# SCHEM_PDB_OFA.net
KiCad netlist of a schematic drawn in Altium Designer
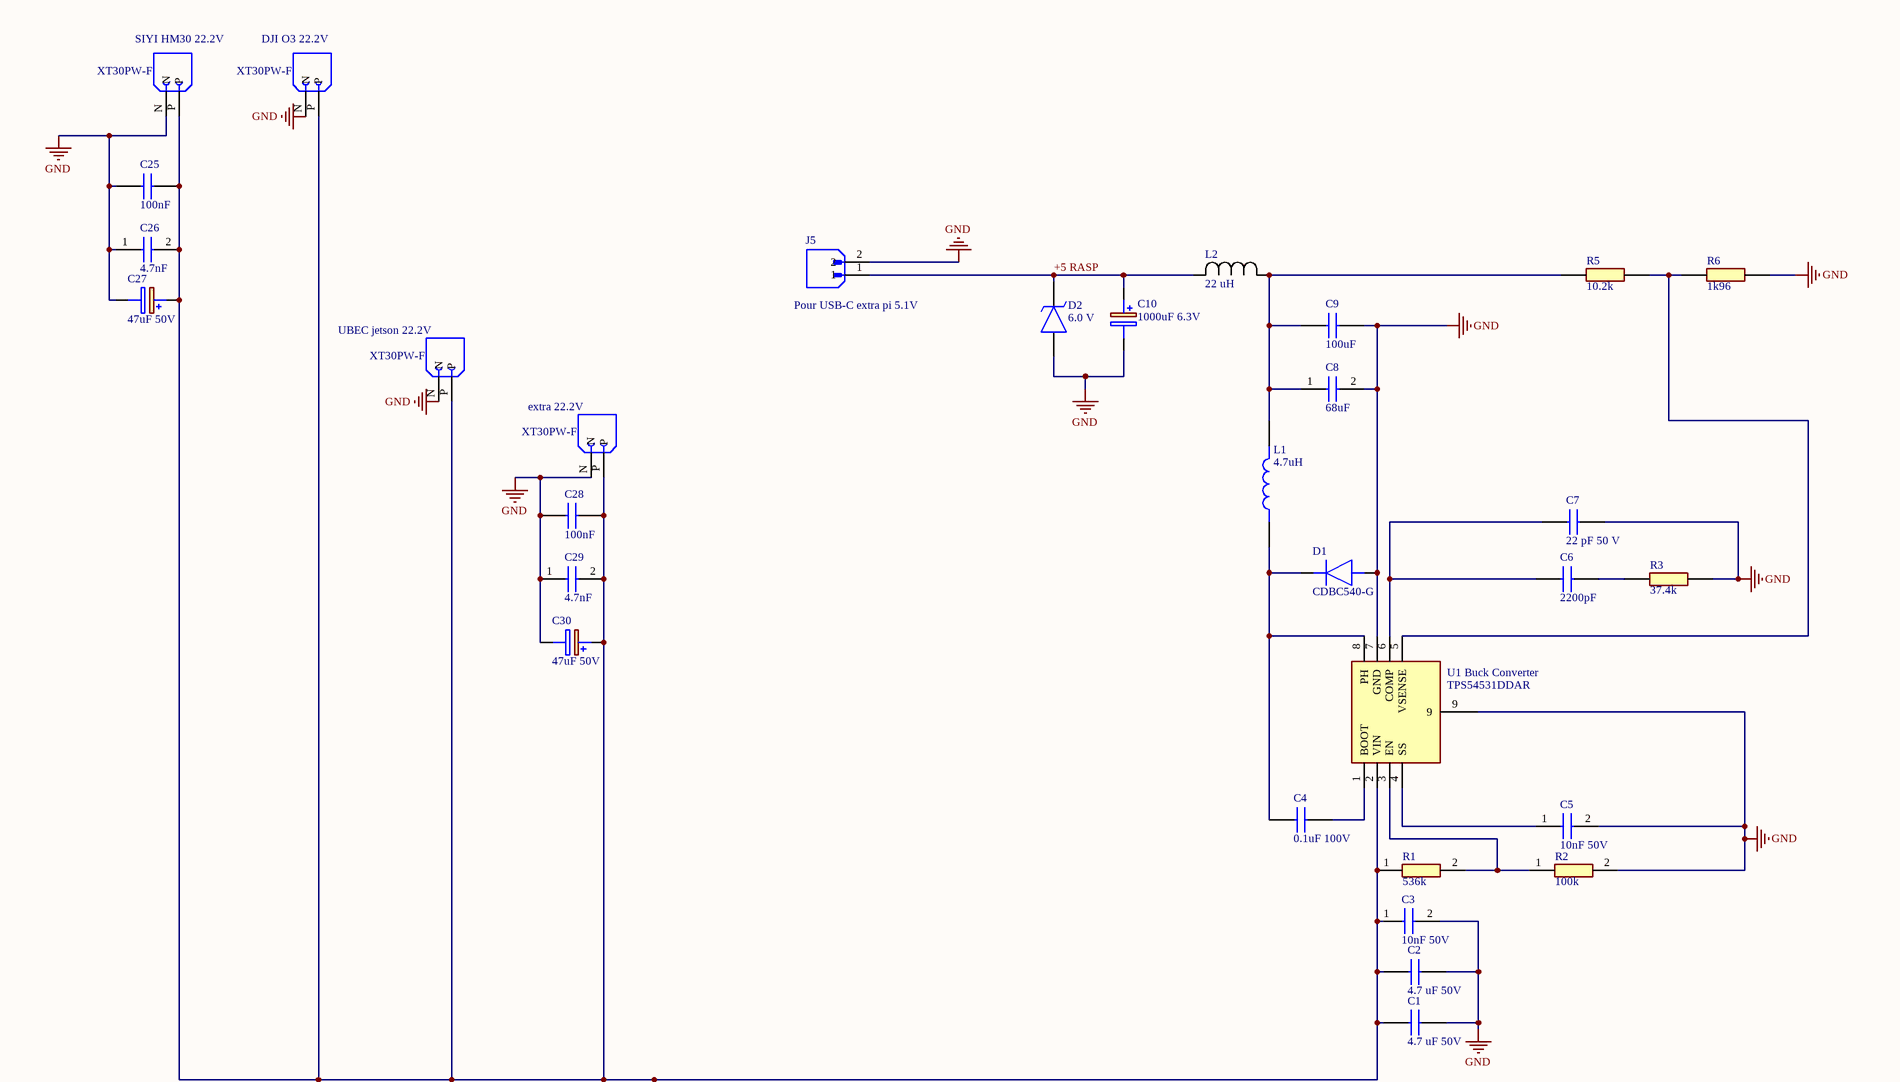
[diagram p0: SCHEM_PDB_OFA.SchDoc, top left]
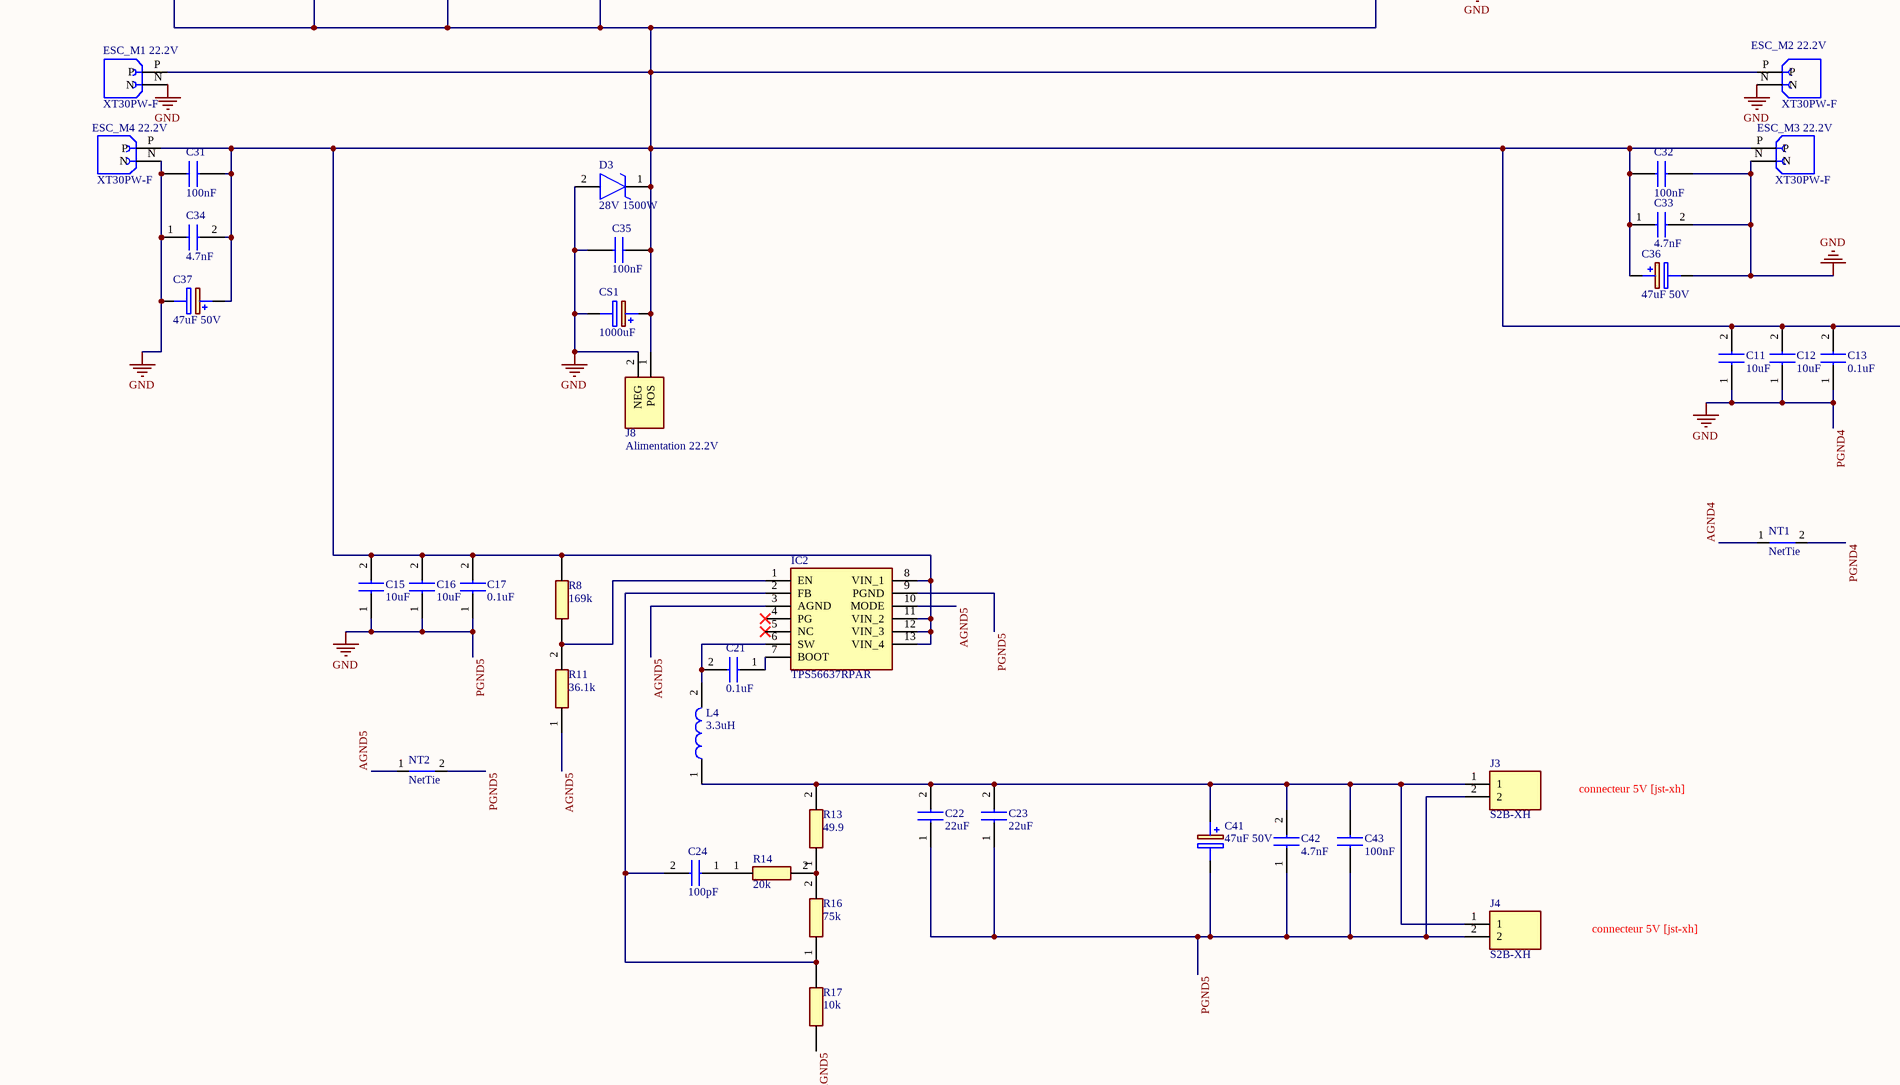
[diagram p1: SCHEM_PDB_OFA.SchDoc, bottom left]
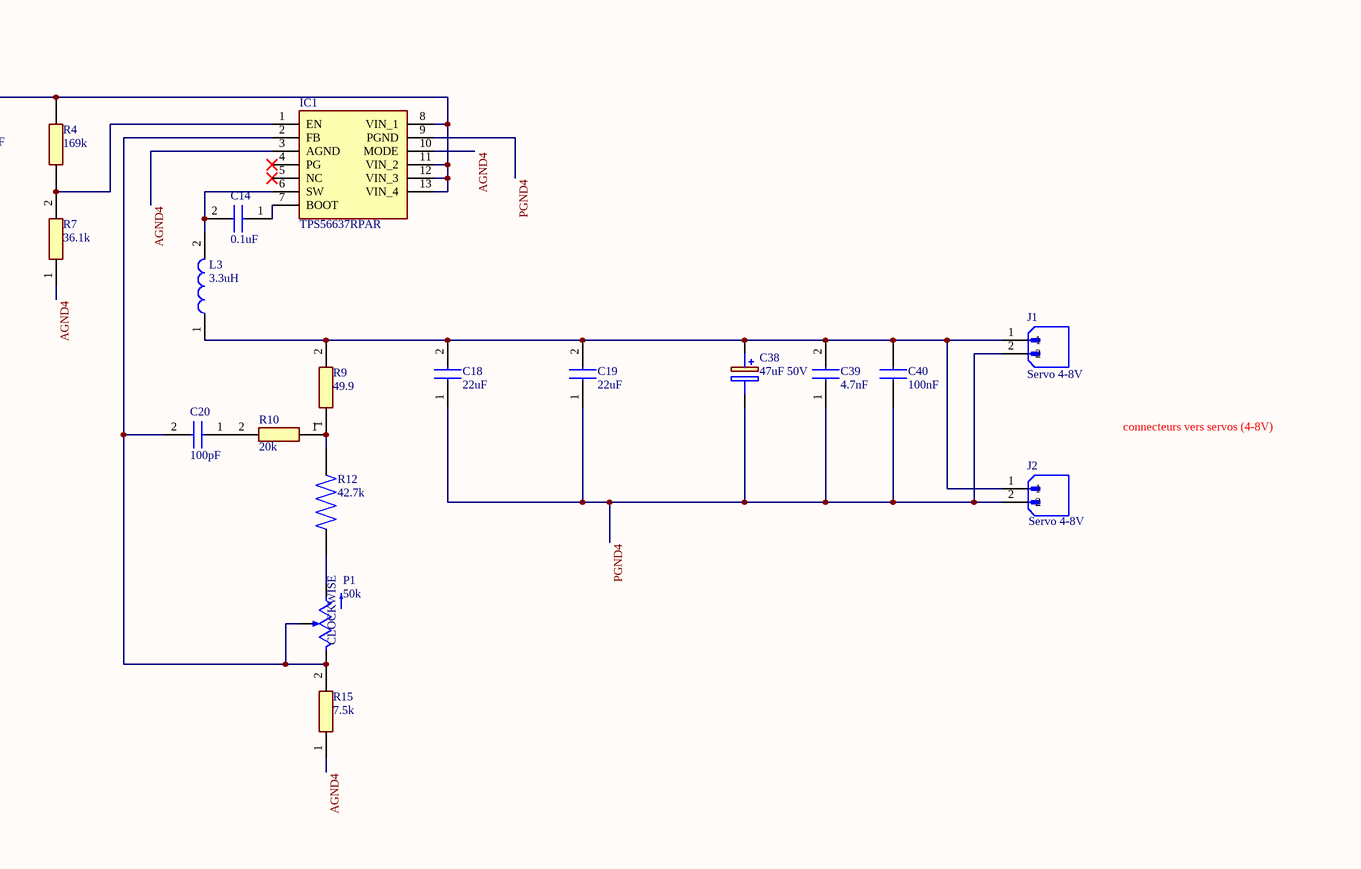
[diagram p2: SCHEM_PDB_OFA.SchDoc, bottom right]

(export (version "E")
  (design (tool "Eeschema 10.0.6"))
  (components
    (comp (ref "C1")
      (value "4.7 uF 50V")
      (footprint "CAPC2012X145N")
      (description "Capacitor")
      (fields
        (field (name "MANUFACTURER_PART_NUMBER") "GRM21BR61H475KE51L")
        (field (name "MOUSER PART NUMBER") "81-GRM21BR61H475KE1L")
      )
      (libsource (lib "Symbol_library") (part "GRM21BR61H475KE51L"))
    )
    (comp (ref "C2")
      (value "4.7 uF 50V")
      (footprint "CAPC2012X145N")
      (description "Capacitor")
      (fields
        (field (name "MANUFACTURER_PART_NUMBER") "GRM21BR61H475KE51L")
        (field (name "MOUSER PART NUMBER") "81-GRM21BR61H475KE1L")
      )
      (libsource (lib "Symbol_library") (part "GRM21BR61H475KE51L"))
    )
    (comp (ref "C3")
      (value "10nF 50V")
      (footprint "CAPC1608X90N")
      (description "Capacitor")
      (fields
        (field (name "MANUFACTURER_PART_NUMBER") "CL10B103KB8NNNC")
        (field (name "MOUSER PART NUMBER") "187-CL10B103KB8NNNC")
      )
      (libsource (lib "Symbol_library") (part "CL10B103KB8NNNC"))
    )
    (comp (ref "C4")
      (value "0.1uF 100V")
      (footprint "CAPC2012X145N")
      (description "Capacitor")
      (fields
        (field (name "MANUFACTURER_PART_NUMBER") "C2012X7R2A104K125AA")
        (field (name "MOUSER PART NUMBER") "810-C2012X7R2A104K")
      )
      (libsource (lib "Symbol_library") (part "C2012X7R2A104K125AA"))
    )
    (comp (ref "C5")
      (value "10nF 50V")
      (footprint "CAPC1608X90N")
      (description "Capacitor")
      (fields
        (field (name "MANUFACTURER_PART_NUMBER") "CL10B103KB8NNNC")
        (field (name "MOUSER PART NUMBER") "187-CL10B103KB8NNNC")
      )
      (libsource (lib "Symbol_library") (part "CL10B103KB8NNNC"))
    )
    (comp (ref "C6")
      (value "2200pF")
      (footprint "CAPC3216X130N")
      (description "Capacitor 2200pF 630V")
      (fields (field (name "MANUFACTURER_PART_NUMBER") "CGA5H4C0G2J222J115AA"))
      (libsource (lib "Symbol_library") (part "CGA5H4C0G2J222J115AA"))
    )
    (comp (ref "C7")
      (value "22 pF 50 V")
      (footprint "CAPC2012X70N")
      (description "Capacitor")
      (fields
        (field (name "MANUFACTURER_PART_NUMBER") "CC0805JRNPO9BN220")
        (field (name "MOUSER PART NUMBER") "603-CC805JRNPO9BN220")
      )
      (libsource (lib "Symbol_library") (part "CC0805JRNPO9BN220"))
    )
    (comp (ref "C8")
      (value "68uF")
      (footprint "CAPC3216X180N")
      (description "Capacitor de 68uF")
      (fields
        (field (name "MANUFACTURER_PART_NUMBER") "C3216X5R0J686M160AB")
        (field (name "MOUSER PART NUMBER") "810-C3216X5R0J686M1B")
      )
      (libsource (lib "Symbol_library") (part "C3216X5R0J686M160AB"))
    )
    (comp (ref "C9")
      (value "100uF")
      (footprint "GRM31x")
      (description "Capacitor")
      (fields
        (field (name "MANUFACTURER_PART_NUMBER") "GRM31CR60J107KEA8L")
        (field (name "MOUSER PART NUMBER") "81-GRM31CR60J107KE8L")
      )
      (libsource (lib "Symbol_library") (part "GRM31CR60J107KEA8L"))
    )
    (comp (ref "C10")
      (value "1000uF 6.3V")
      (footprint "CAPAE830X1050N")
      (description "Capacitor Polarised")
      (fields
        (field (name "MANUFACTURER_PART_NUMBER") "UCD0J102MNL1GS")
        (field (name "MOUSER PART NUMBER") "647-UCD0J102MNL1GS")
      )
      (libsource (lib "Symbol_library") (part "UCD0J102MNL1GS"))
    )
    (comp (ref "C11")
      (value "10uF")
      (footprint "CAPC3225X280N")
      (description "Capacitor")
      (fields (field (name "MANUFACTURER_PART_NUMBER") "AGC1210X7R500-106KNE"))
      (libsource (lib "Symbol_library") (part "AGC1210X7R500-106KNE"))
    )
    (comp (ref "C12")
      (value "10uF")
      (footprint "CAPC3225X280N")
      (description "Capacitor")
      (fields (field (name "MANUFACTURER_PART_NUMBER") "AGC1210X7R500-106KNE"))
      (libsource (lib "Symbol_library") (part "AGC1210X7R500-106KNE"))
    )
    (comp (ref "C13")
      (value "0.1uF")
      (footprint "C0603")
      (description "Capacitor")
      (fields
        (field (name "MANUFACTURER_PART_NUMBER") "C0603C104K5RACTU")
        (field (name "MOUSER PART NUMBER") "80-C0603C104K5R")
      )
      (libsource (lib "Symbol_library") (part "C0603C104K5RACTU"))
    )
    (comp (ref "C14")
      (value "0.1uF")
      (footprint "C0603")
      (description "Capacitor")
      (fields
        (field (name "MANUFACTURER_PART_NUMBER") "C0603C104K5RACTU")
        (field (name "MOUSER PART NUMBER") "80-C0603C104K5R")
      )
      (libsource (lib "Symbol_library") (part "C0603C104K5RACTU"))
    )
    (comp (ref "C15")
      (value "10uF")
      (footprint "CAPC3225X280N")
      (description "Capacitor")
      (fields (field (name "MANUFACTURER_PART_NUMBER") "AGC1210X7R500-106KNE"))
      (libsource (lib "Symbol_library") (part "AGC1210X7R500-106KNE"))
    )
    (comp (ref "C16")
      (value "10uF")
      (footprint "CAPC3225X280N")
      (description "Capacitor")
      (fields (field (name "MANUFACTURER_PART_NUMBER") "AGC1210X7R500-106KNE"))
      (libsource (lib "Symbol_library") (part "AGC1210X7R500-106KNE"))
    )
    (comp (ref "C17")
      (value "0.1uF")
      (footprint "C0603")
      (description "Capacitor")
      (fields
        (field (name "MANUFACTURER_PART_NUMBER") "C0603C104K5RACTU")
        (field (name "MOUSER PART NUMBER") "80-C0603C104K5R")
      )
      (libsource (lib "Symbol_library") (part "C0603C104K5RACTU"))
    )
    (comp (ref "C18")
      (value "22uF")
      (footprint "CAPC2012X145N")
      (description "Capacitor, 35V")
      (fields
        (field (name "MANUFACTURER_PART_NUMBER") "C2012X5R1V226M125AC")
        (field (name "MOUSER PART NUMBER") "810-C2012X5R1V226MAC")
      )
      (libsource (lib "Symbol_library") (part "C2012X5R1V226M125AC"))
    )
    (comp (ref "C19")
      (value "22uF")
      (footprint "CAPC2012X145N")
      (description "Capacitor, 35V")
      (fields
        (field (name "MANUFACTURER_PART_NUMBER") "C2012X5R1V226M125AC")
        (field (name "MOUSER PART NUMBER") "810-C2012X5R1V226MAC")
      )
      (libsource (lib "Symbol_library") (part "C2012X5R1V226M125AC"))
    )
    (comp (ref "C20")
      (value "100pF")
      (footprint "GRM1885C1H101JA01D")
      (description "Capacitor")
      (fields
        (field (name "MANUFACTURER_PART_NUMBER") "GRM1885C1H101JA01D")
        (field (name "MOUSER PART NUMBER") "81-GRM39C101J50")
      )
      (libsource (lib "Symbol_library") (part "GRM1885C1H101JA01D"))
    )
    (comp (ref "C21")
      (value "0.1uF")
      (footprint "C0603")
      (description "Capacitor")
      (fields
        (field (name "MANUFACTURER_PART_NUMBER") "C0603C104K5RACTU")
        (field (name "MOUSER PART NUMBER") "80-C0603C104K5R")
      )
      (libsource (lib "Symbol_library") (part "C0603C104K5RACTU"))
    )
    (comp (ref "C22")
      (value "22uF")
      (footprint "CAPC2012X145N")
      (description "Capacitor, 35V")
      (fields
        (field (name "MANUFACTURER_PART_NUMBER") "C2012X5R1V226M125AC")
        (field (name "MOUSER PART NUMBER") "810-C2012X5R1V226MAC")
      )
      (libsource (lib "Symbol_library") (part "C2012X5R1V226M125AC"))
    )
    (comp (ref "C23")
      (value "22uF")
      (footprint "CAPC2012X145N")
      (description "Capacitor, 35V")
      (fields
        (field (name "MANUFACTURER_PART_NUMBER") "C2012X5R1V226M125AC")
        (field (name "MOUSER PART NUMBER") "810-C2012X5R1V226MAC")
      )
      (libsource (lib "Symbol_library") (part "C2012X5R1V226M125AC"))
    )
    (comp (ref "C24")
      (value "100pF")
      (footprint "GRM1885C1H101JA01D")
      (description "Capacitor")
      (fields
        (field (name "MANUFACTURER_PART_NUMBER") "GRM1885C1H101JA01D")
        (field (name "MOUSER PART NUMBER") "81-GRM39C101J50")
      )
      (libsource (lib "Symbol_library") (part "GRM1885C1H101JA01D"))
    )
    (comp (ref "C25")
      (value "100nF")
      (footprint "C1206")
      (description "Capacitor, 100V max")
      (fields
        (field (name "MANUFACTURER_PART_NUMBER") "C1206C104K1RACTU")
        (field (name "MOUSER PART NUMBER") "80-C1206C104K1R")
      )
      (libsource (lib "Symbol_library") (part "C1206C104K1RACTU"))
    )
    (comp (ref "C26")
      (value "4.7nF")
      (footprint "C1206")
      (description "Capacitor, 50V max")
      (fields
        (field (name "MANUFACTURER_PART_NUMBER") "C1206C472K5RACTU")
        (field (name "MOUSER PART NUMBER") "80-C1206C472K5R")
      )
      (libsource (lib "Symbol_library") (part "C1206C472K5RACTU"))
    )
    (comp (ref "C27")
      (value "47uF 50V")
      (footprint "CAPPRD250W50D655H1250")
      (description "Capacitor Polarised, 47uF, 50V")
      (fields
        (field (name "MANUFACTURER_PART_NUMBER") "50YXJ47M6.3X11")
        (field (name "MOUSER PART NUMBER") "232-50YXJ47M6.3X11")
      )
      (libsource (lib "") (part "50YXJ47M6.3X11_1"))
    )
    (comp (ref "C28")
      (value "100nF")
      (footprint "C1206")
      (description "Capacitor, 100V max")
      (fields
        (field (name "MANUFACTURER_PART_NUMBER") "C1206C104K1RACTU")
        (field (name "MOUSER PART NUMBER") "80-C1206C104K1R")
      )
      (libsource (lib "Symbol_library") (part "C1206C104K1RACTU"))
    )
    (comp (ref "C29")
      (value "4.7nF")
      (footprint "C1206")
      (description "Capacitor, 50V max")
      (fields
        (field (name "MANUFACTURER_PART_NUMBER") "C1206C472K5RACTU")
        (field (name "MOUSER PART NUMBER") "80-C1206C472K5R")
      )
      (libsource (lib "Symbol_library") (part "C1206C472K5RACTU"))
    )
    (comp (ref "C30")
      (value "47uF 50V")
      (footprint "CAPPRD250W50D655H1250")
      (description "Capacitor Polarised, 47uF, 50V")
      (fields
        (field (name "MANUFACTURER_PART_NUMBER") "50YXJ47M6.3X11")
        (field (name "MOUSER PART NUMBER") "232-50YXJ47M6.3X11")
      )
      (libsource (lib "") (part "50YXJ47M6.3X11_1"))
    )
    (comp (ref "C31")
      (value "100nF")
      (footprint "C1206")
      (description "Capacitor, 100V max")
      (fields
        (field (name "MANUFACTURER_PART_NUMBER") "C1206C104K1RACTU")
        (field (name "MOUSER PART NUMBER") "80-C1206C104K1R")
      )
      (libsource (lib "Symbol_library") (part "C1206C104K1RACTU"))
    )
    (comp (ref "C32")
      (value "100nF")
      (footprint "C1206")
      (description "Capacitor, 100V max")
      (fields
        (field (name "MANUFACTURER_PART_NUMBER") "C1206C104K1RACTU")
        (field (name "MOUSER PART NUMBER") "80-C1206C104K1R")
      )
      (libsource (lib "Symbol_library") (part "C1206C104K1RACTU"))
    )
    (comp (ref "C33")
      (value "4.7nF")
      (footprint "C1206")
      (description "Capacitor, 50V max")
      (fields
        (field (name "MANUFACTURER_PART_NUMBER") "C1206C472K5RACTU")
        (field (name "MOUSER PART NUMBER") "80-C1206C472K5R")
      )
      (libsource (lib "Symbol_library") (part "C1206C472K5RACTU"))
    )
    (comp (ref "C34")
      (value "4.7nF")
      (footprint "C1206")
      (description "Capacitor, 50V max")
      (fields
        (field (name "MANUFACTURER_PART_NUMBER") "C1206C472K5RACTU")
        (field (name "MOUSER PART NUMBER") "80-C1206C472K5R")
      )
      (libsource (lib "Symbol_library") (part "C1206C472K5RACTU"))
    )
    (comp (ref "C35")
      (value "100nF")
      (footprint "C1206")
      (description "Capacitor, 100V max")
      (fields
        (field (name "MANUFACTURER_PART_NUMBER") "C1206C104K1RACTU")
        (field (name "MOUSER PART NUMBER") "80-C1206C104K1R")
      )
      (libsource (lib "Symbol_library") (part "C1206C104K1RACTU"))
    )
    (comp (ref "C36")
      (value "47uF 50V")
      (footprint "CAPPRD250W50D655H1250")
      (description "Capacitor Polarised, 47uF, 50V")
      (fields
        (field (name "MANUFACTURER_PART_NUMBER") "50YXJ47M6.3X11")
        (field (name "MOUSER PART NUMBER") "232-50YXJ47M6.3X11")
      )
      (libsource (lib "Symbol_library") (part "50YXJ47M6.3X11"))
    )
    (comp (ref "C37")
      (value "47uF 50V")
      (footprint "CAPPRD250W50D655H1250")
      (description "Capacitor Polarised, 47uF, 50V")
      (fields
        (field (name "MANUFACTURER_PART_NUMBER") "50YXJ47M6.3X11")
        (field (name "MOUSER PART NUMBER") "232-50YXJ47M6.3X11")
      )
      (libsource (lib "") (part "50YXJ47M6.3X11_1"))
    )
    (comp (ref "C38")
      (value "47uF 50V")
      (footprint "CAPPRD250W50D655H1250")
      (description "Capacitor Polarised, 47uF, 50V")
      (fields
        (field (name "MANUFACTURER_PART_NUMBER") "50YXJ47M6.3X11")
        (field (name "MOUSER PART NUMBER") "232-50YXJ47M6.3X11")
      )
      (libsource (lib "") (part "50YXJ47M6.3X11_2"))
    )
    (comp (ref "C39")
      (value "4.7nF")
      (footprint "C1206")
      (description "Capacitor, 50V max")
      (fields
        (field (name "MANUFACTURER_PART_NUMBER") "C1206C472K5RACTU")
        (field (name "MOUSER PART NUMBER") "80-C1206C472K5R")
      )
      (libsource (lib "Symbol_library") (part "C1206C472K5RACTU"))
    )
    (comp (ref "C40")
      (value "100nF")
      (footprint "C1206")
      (description "Capacitor, 100V max")
      (fields
        (field (name "MANUFACTURER_PART_NUMBER") "C1206C104K1RACTU")
        (field (name "MOUSER PART NUMBER") "80-C1206C104K1R")
      )
      (libsource (lib "Symbol_library") (part "C1206C104K1RACTU"))
    )
    (comp (ref "C41")
      (value "47uF 50V")
      (footprint "CAPPRD250W50D655H1250")
      (description "Capacitor Polarised, 47uF, 50V")
      (fields
        (field (name "MANUFACTURER_PART_NUMBER") "50YXJ47M6.3X11")
        (field (name "MOUSER PART NUMBER") "232-50YXJ47M6.3X11")
      )
      (libsource (lib "") (part "50YXJ47M6.3X11_2"))
    )
    (comp (ref "C42")
      (value "4.7nF")
      (footprint "C1206")
      (description "Capacitor, 50V max")
      (fields
        (field (name "MANUFACTURER_PART_NUMBER") "C1206C472K5RACTU")
        (field (name "MOUSER PART NUMBER") "80-C1206C472K5R")
      )
      (libsource (lib "Symbol_library") (part "C1206C472K5RACTU"))
    )
    (comp (ref "C43")
      (value "100nF")
      (footprint "C1206")
      (description "Capacitor, 100V max")
      (fields
        (field (name "MANUFACTURER_PART_NUMBER") "C1206C104K1RACTU")
        (field (name "MOUSER PART NUMBER") "80-C1206C104K1R")
      )
      (libsource (lib "Symbol_library") (part "C1206C104K1RACTU"))
    )
    (comp (ref "CS1")
      (value "1000uF")
      (footprint "CAPPRD500W60D1025H2150")
      (description "Capacitor Polarised")
      (fields
        (field (name "MANUFACTURER_PART_NUMBER") "35PX1000MEFC10X20")
        (field (name "MOUSER PART NUMBER") "232-35PX1000MEFC10X2")
      )
      (libsource (lib "Symbol_library") (part "35PX1000MEFC10X20"))
    )
    (comp (ref "D1")
      (value "CDBC540-G")
      (footprint "DIOM8059X290N")
      (description "Diode")
      (fields (field (name "MOUSER PART NUMBER") "750-CDBC540-G"))
      (libsource (lib "Symbol_library") (part "CDBC540-G"))
    )
    (comp (ref "D2")
      (value "6.0 V")
      (footprint "SMBJ12A")
      (description "TVS Diode (Uni-directional)")
      (fields (field (name "MANUFACTURER_PART_NUMBER") "SMBJ6.0A"))
      (libsource (lib "Symbol_library") (part "SMBJ6.0A"))
    )
    (comp (ref "D3")
      (value "28V 1500W")
      (footprint "DIOM7959X262N")
      (description "TVS Diode, 1500W, 28V")
      (fields
        (field (name "MANUFACTURER_PART_NUMBER") "SMCJ28A")
        (field (name "MOUSER PART NUMBER") "652-SMCJ28A")
      )
      (libsource (lib "Symbol_library") (part "SMCJ28A"))
    )
    (comp (ref "DJI O3 22.2V")
      (value "XT30PW-F")
      (footprint "AMASS_XT30PW-F")
      (description "Socket; DC supply; XT30; female; PIN: 2; on PCBs; THT; yellow; 15A")
      (fields (field (name "MF") "amass"))
      (libsource (lib "Symbol_library") (part "XT30PW-F"))
    )
    (comp (ref "ESC_M1 22.2V")
      (value "XT30PW-F")
      (footprint "AMASS_XT30PW-F")
      (description "Socket; DC supply; XT30; female; PIN: 2; on PCBs; THT; yellow; 15A")
      (fields (field (name "MF") "amass"))
      (libsource (lib "Symbol_library") (part "XT30PW-F"))
    )
    (comp (ref "ESC_M2 22.2V")
      (value "XT30PW-F")
      (footprint "AMASS_XT30PW-F")
      (description "Socket; DC supply; XT30; female; PIN: 2; on PCBs; THT; yellow; 15A")
      (fields (field (name "MF") "amass"))
      (libsource (lib "") (part "XT30PW-F_1"))
    )
    (comp (ref "ESC_M3 22.2V")
      (value "XT30PW-F")
      (footprint "AMASS_XT30PW-F")
      (description "Socket; DC supply; XT30; female; PIN: 2; on PCBs; THT; yellow; 15A")
      (fields (field (name "MF") "amass"))
      (libsource (lib "") (part "XT30PW-F_1"))
    )
    (comp (ref "ESC_M4 22.2V")
      (value "XT30PW-F")
      (footprint "AMASS_XT30PW-F")
      (description "Socket; DC supply; XT30; female; PIN: 2; on PCBs; THT; yellow; 15A")
      (fields (field (name "MF") "amass"))
      (libsource (lib "Symbol_library") (part "XT30PW-F"))
    )
    (comp (ref "extra 22.2V")
      (value "XT30PW-F")
      (footprint "AMASS_XT30PW-F")
      (description "Socket; DC supply; XT30; female; PIN: 2; on PCBs; THT; yellow; 15A")
      (fields (field (name "MF") "amass"))
      (libsource (lib "Symbol_library") (part "XT30PW-F"))
    )
    (comp (ref "IC1")
      (value "TPS56637RPAR")
      (footprint "TPS56637RPAR")
      (description "Integrated Circuit")
      (fields (field (name "MOUSER PART NUMBER") "595-TPS56637RPAR"))
      (libsource (lib "Symbol_library") (part "TPS56637RPAR"))
    )
    (comp (ref "IC2")
      (value "TPS56637RPAR")
      (footprint "TPS56637RPAR")
      (description "Integrated Circuit")
      (fields (field (name "MOUSER PART NUMBER") "595-TPS56637RPAR"))
      (libsource (lib "Symbol_library") (part "TPS56637RPAR"))
    )
    (comp (ref "J1")
      (value "Servo 4-8V")
      (footprint "JST_B2PS-VH_(LF)(SN)")
      (description "Connector Header Through Hole, Right Angle 2 position 0.156 (3.96mm)")
      (fields (field (name "MF") "JST") (field (name "MP") "B2PS-VH (LF)(SN)"))
      (libsource (lib "") (part "B2PS-VH_(LF)(SN)_1"))
    )
    (comp (ref "J2")
      (value "Servo 4-8V")
      (footprint "JST_B2PS-VH_(LF)(SN)")
      (description "Connector Header Through Hole, Right Angle 2 position 0.156 (3.96mm)")
      (fields (field (name "MF") "JST") (field (name "MP") "B2PS-VH (LF)(SN)"))
      (libsource (lib "") (part "B2PS-VH_(LF)(SN)_1"))
    )
    (comp (ref "J3")
      (value "S2B-XH")
      (footprint "S2BXHA1LFSN")
      (description "CONN HEADER R/A 2POS 2.5MM")
      (fields (field (name "MANUFACTURER_PART_NUMBER") "S2B-XH-A-1(LF)(SN)"))
      (libsource (lib "Symbol_library") (part "S2B-XH-A-1_LF__SN_"))
    )
    (comp (ref "J4")
      (value "S2B-XH")
      (footprint "S2BXHA1LFSN")
      (description "CONN HEADER R/A 2POS 2.5MM")
      (fields (field (name "MANUFACTURER_PART_NUMBER") "S2B-XH-A-1(LF)(SN)"))
      (libsource (lib "Symbol_library") (part "S2B-XH-A-1_LF__SN_"))
    )
    (comp (ref "J5")
      (value "Pour USB-C extra pi 5.1V")
      (footprint "JST_B2PS-VH_(LF)(SN)")
      (description "Connector Header Through Hole, Right Angle 2 position 0.156 (3.96mm)")
      (fields (field (name "MF") "JST") (field (name "MP") "B2PS-VH (LF)(SN)"))
      (libsource (lib "Symbol_library") (part "B2PS-VH_(LF)(SN)"))
    )
    (comp (ref "J8")
      (value "Alimentation 22.2V")
      (footprint "AMASS_XT60PW-M")
      (description "Socket, DC supply, male, PIN: 2")
      (fields (field (name "MF") "AMASS") (field (name "MP") "XT60PW-M"))
      (libsource (lib "Symbol_library") (part "XT60PW-M"))
    )
    (comp (ref "L1")
      (value "4.7uH")
      (footprint "IND_ECS-MPIL0530-4R7MC")
      (description "4.7 µH Shielded Molded Inductor 5 A 60mOhm Max Nonstandard -")
      (fields (field (name "MF") "ECS Inc.") (field (name "MP") "ECS-MPIL0530-4R7MC"))
      (libsource (lib "Symbol_library") (part "ECS-MPIL0530-4R7MC"))
    )
    (comp (ref "L2")
      (value "22 uH")
      (footprint "IND_104CDMCCDS_SUM")
      (description "Bobine de 22 uH, 5 A")
      (fields
        (field (name "MANUFACTURER_PART_NUMBER") "104CDMCCDS-220MC")
        (field (name "COPYRIGHT") "Copyright (C) 2025 Ultra Librarian. All rights reserved.")
      )
      (libsource (lib "Symbol_library") (part "104CDMCCDS-220MC"))
    )
    (comp (ref "L3")
      (value "3.3uH")
      (footprint "INDM3225X240N")
      (description "Inductor")
      (fields (field (name "MANUFACTURER_PART_NUMBER") "NLV32T-3R3J-EF"))
      (libsource (lib "Symbol_library") (part "NLV32T-3R3J-EF"))
    )
    (comp (ref "L4")
      (value "3.3uH")
      (footprint "INDM3225X240N")
      (description "Inductor")
      (fields (field (name "MANUFACTURER_PART_NUMBER") "NLV32T-3R3J-EF"))
      (libsource (lib "Symbol_library") (part "NLV32T-3R3J-EF"))
    )
    (comp (ref "NT1")
      (value "NetTie")
      (footprint "NetTie")
      (description "Net Tie")
      (libsource (lib "Symbol_library") (part "NetTie"))
    )
    (comp (ref "NT2")
      (value "NetTie")
      (footprint "NetTie")
      (description "Net Tie")
      (libsource (lib "Symbol_library") (part "NetTie"))
    )
    (comp (ref "P1")
      (value "50k")
      (footprint "TRIM_3361P-1-503GLF")
      (description "Potentiometer 50k ohms")
      (libsource (lib "Symbol_library") (part "TRIM_3361P-1-503GLF"))
    )
    (comp (ref "R1")
      (value "536k")
      (footprint "ERA6AEB101V")
      (description "Resistor")
      (fields (field (name "MANUFACTURER_PART_NUMBER") "ERA6AEB5363V"))
      (libsource (lib "Symbol_library") (part "ERA-6AEB5363V"))
    )
    (comp (ref "R2")
      (value "100k")
      (footprint "RESC3216X71N")
      (description "Resistor")
      (fields
        (field (name "MANUFACTURER_PART_NUMBER") "TNPW1206100KBEEA")
        (field (name "MOUSER PART NUMBER") "71-TNPW1206100KBEEA")
      )
      (libsource (lib "Symbol_library") (part "TNPW1206100KBEEA"))
    )
    (comp (ref "R3")
      (value "37.4k")
      (footprint "RESC2012X50N")
      (description "Resistor")
      (fields
        (field (name "MANUFACTURER_PART_NUMBER") "CRCW080537K4FKEA")
        (field (name "MOUSER PART NUMBER") "71-CRCW0805-37.4K-E3")
      )
      (libsource (lib "Symbol_library") (part "CRCW080537K4FKEA"))
    )
    (comp (ref "R4")
      (value "169k")
      (footprint "RESC2012X50N")
      (description "Resistor")
      (fields
        (field (name "MANUFACTURER_PART_NUMBER") "CRCW08051K96FKEA")
        (field (name "MOUSER PART NUMBER") "71-CRCW08051K96FKEA")
      )
      (libsource (lib "Symbol_library") (part "CRCW08051K96FKEA"))
    )
    (comp (ref "R5")
      (value "10.2k")
      (footprint "RESC2012X50N")
      (description "Resistor")
      (fields
        (field (name "MANUFACTURER_PART_NUMBER") "CRCW080510K2FKEA")
        (field (name "MOUSER PART NUMBER") "71-CRCW0805-10.2K-E3")
      )
      (libsource (lib "Symbol_library") (part "CRCW080510K2FKEA"))
    )
    (comp (ref "R6")
      (value "1k96")
      (footprint "RESC2012X50N")
      (description "Resistor")
      (fields
        (field (name "MANUFACTURER_PART_NUMBER") "CRCW08051K96FKEA")
        (field (name "MOUSER PART NUMBER") "71-CRCW08051K96FKEA")
      )
      (libsource (lib "") (part "CRCW08051K96FKEA_1"))
    )
    (comp (ref "R7")
      (value "36.1k")
      (footprint "RESC1608X51N")
      (description "Resistor")
      (fields (field (name "MANUFACTURER_PART_NUMBER") "PTN0603E3612BST1"))
      (libsource (lib "Symbol_library") (part "PTN0603E3612BST1"))
    )
    (comp (ref "R8")
      (value "169k")
      (footprint "RESC2012X50N")
      (description "Resistor")
      (fields
        (field (name "MANUFACTURER_PART_NUMBER") "CRCW08051K96FKEA")
        (field (name "MOUSER PART NUMBER") "71-CRCW08051K96FKEA")
      )
      (libsource (lib "Symbol_library") (part "CRCW08051K96FKEA"))
    )
    (comp (ref "R9")
      (value "49.9")
      (footprint "RESC3016X65N")
      (description "Resistor")
      (fields
        (field (name "MANUFACTURER_PART_NUMBER") "RNCF1206TKY49R9")
        (field (name "MOUSER PART NUMBER") "708-RNCF1206TKY49R9")
      )
      (libsource (lib "Symbol_library") (part "RNCF1206TKY49R9"))
    )
    (comp (ref "R10")
      (value "20k")
      (footprint "RESC2012X60N")
      (description "Resistor")
      (fields
        (field (name "MANUFACTURER_PART_NUMBER") "RK73H2ATTD2002F")
        (field (name "MOUSER PART NUMBER") "660-RK73H2ATTD2002F")
      )
      (libsource (lib "Symbol_library") (part "RK73H2ATTD2002F"))
    )
    (comp (ref "R11")
      (value "36.1k")
      (footprint "RESC1608X51N")
      (description "Resistor")
      (fields (field (name "MANUFACTURER_PART_NUMBER") "PTN0603E3612BST1"))
      (libsource (lib "Symbol_library") (part "PTN0603E3612BST1"))
    )
    (comp (ref "R12")
      (value "42.7k")
      (footprint "RESC2012X60N")
      (fields (field (name "MP") "RN73R2ATTD4272D25"))
      (libsource (lib "Symbol_library") (part "RN73R2ATTD4272D25"))
    )
    (comp (ref "R13")
      (value "49.9")
      (footprint "RESC3016X65N")
      (description "Resistor")
      (fields
        (field (name "MANUFACTURER_PART_NUMBER") "RNCF1206TKY49R9")
        (field (name "MOUSER PART NUMBER") "708-RNCF1206TKY49R9")
      )
      (libsource (lib "Symbol_library") (part "RNCF1206TKY49R9"))
    )
    (comp (ref "R14")
      (value "20k")
      (footprint "RESC2012X60N")
      (description "Resistor")
      (fields
        (field (name "MANUFACTURER_PART_NUMBER") "RK73H2ATTD2002F")
        (field (name "MOUSER PART NUMBER") "660-RK73H2ATTD2002F")
      )
      (libsource (lib "") (part "RK73H2ATTD2002F_1"))
    )
    (comp (ref "R15")
      (value "7.5k")
      (footprint "RESC1608X55N")
      (description "Resistor")
      (fields
        (field (name "MANUFACTURER_PART_NUMBER") "RC0603FR-077K5L")
        (field (name "MOUSER PART NUMBER") "603-RC0603FR-077K5L")
      )
      (libsource (lib "Symbol_library") (part "RC0603FR-077K5L"))
    )
    (comp (ref "R16")
      (value "75k")
      (footprint "RESC3216X75N")
      (description "Resistor")
      (fields
        (field (name "MANUFACTURER_PART_NUMBER") "CR1206-FX-7502ELF")
        (field (name "MOUSER PART NUMBER") "652-CR1206FX-7502ELF")
      )
      (libsource (lib "Symbol_library") (part "CR1206-FX-7502ELF"))
    )
    (comp (ref "R17")
      (value "10k")
      (footprint "RESC2012X60N")
      (description "Resistor")
      (fields
        (field (name "MANUFACTURER_PART_NUMBER") "CRCW080510K0FKEAHP")
        (field (name "MOUSER PART NUMBER") "71-CRCW080510K0FKEAH")
      )
      (libsource (lib "Symbol_library") (part "CRCW080510K0FKEAHP"))
    )
    (comp (ref "SIYI HM30 22.2V")
      (value "XT30PW-F")
      (footprint "AMASS_XT30PW-F")
      (description "Socket; DC supply; XT30; female; PIN: 2; on PCBs; THT; yellow; 15A")
      (fields (field (name "MF") "amass"))
      (libsource (lib "Symbol_library") (part "XT30PW-F"))
    )
    (comp (ref "U1 Buck Converter")
      (value "TPS54531DDAR")
      (footprint "SOIC127P600X175-8N")
      (description "Power Supply")
      (fields (field (name "MOUSER PART NUMBER") "595-TPS54531DDAR"))
      (libsource (lib "Symbol_library") (part "TPS54531DDAR"))
    )
    (comp (ref "UBEC jetson 22.2V")
      (value "XT30PW-F")
      (footprint "AMASS_XT30PW-F")
      (description "Socket; DC supply; XT30; female; PIN: 2; on PCBs; THT; yellow; 15A")
      (fields (field (name "MF") "amass"))
      (libsource (lib "Symbol_library") (part "XT30PW-F"))
    )
  )
  (nets
    (net (code "1") (name "/+5 RASP") (class "Default")
      (node (ref "C10") (pin "1") (pinfunction "+_1") (pintype "passive"))
      (node (ref "D2") (pin "1") (pinfunction "K_1") (pintype "passive"))
      (node (ref "J5") (pin "1") (pinfunction "1_1") (pintype "passive"))
      (node (ref "L2") (pin "2") (pinfunction "2_2") (pintype "passive"))
    )
    (net (code "2") (name "/AGND4") (class "Default")
      (node (ref "IC1") (pin "10") (pinfunction "MODE_10") (pintype "passive"))
      (node (ref "IC1") (pin "3") (pinfunction "AGND_3") (pintype "passive"))
      (node (ref "NT1") (pin "1") (pintype "passive"))
      (node (ref "R15") (pin "1") (pinfunction "1_1") (pintype "passive"))
      (node (ref "R7") (pin "1") (pinfunction "1_1") (pintype "passive"))
    )
    (net (code "3") (name "/AGND5") (class "Default")
      (node (ref "IC2") (pin "10") (pinfunction "MODE_10") (pintype "passive"))
      (node (ref "IC2") (pin "3") (pinfunction "AGND_3") (pintype "passive"))
      (node (ref "NT2") (pin "1") (pintype "passive"))
      (node (ref "R11") (pin "1") (pinfunction "1_1") (pintype "passive"))
      (node (ref "R17") (pin "1") (pinfunction "1_1") (pintype "passive"))
    )
    (net (code "4") (name "GND") (class "Default")
      (node (ref "C1") (pin "1") (pinfunction "1_1") (pintype "passive"))
      (node (ref "C10") (pin "2") (pinfunction "-_2") (pintype "passive"))
      (node (ref "C11") (pin "1") (pinfunction "1_1") (pintype "passive"))
      (node (ref "C12") (pin "1") (pinfunction "1_1") (pintype "passive"))
      (node (ref "C13") (pin "1") (pinfunction "1_1") (pintype "passive"))
      (node (ref "C15") (pin "1") (pinfunction "1_1") (pintype "passive"))
      (node (ref "C16") (pin "1") (pinfunction "1_1") (pintype "passive"))
      (node (ref "C17") (pin "1") (pinfunction "1_1") (pintype "passive"))
      (node (ref "C18") (pin "1") (pinfunction "1_1") (pintype "passive"))
      (node (ref "C19") (pin "1") (pinfunction "1_1") (pintype "passive"))
      (node (ref "C2") (pin "1") (pinfunction "1_1") (pintype "passive"))
      (node (ref "C22") (pin "1") (pinfunction "1_1") (pintype "passive"))
      (node (ref "C23") (pin "1") (pinfunction "1_1") (pintype "passive"))
      (node (ref "C25") (pin "1") (pinfunction "1_1") (pintype "passive"))
      (node (ref "C26") (pin "1") (pinfunction "1_1") (pintype "passive"))
      (node (ref "C27") (pin "2") (pinfunction "-_2") (pintype "passive"))
      (node (ref "C28") (pin "1") (pinfunction "1_1") (pintype "passive"))
      (node (ref "C29") (pin "1") (pinfunction "1_1") (pintype "passive"))
      (node (ref "C3") (pin "2") (pinfunction "2_2") (pintype "passive"))
      (node (ref "C30") (pin "2") (pinfunction "-_2") (pintype "passive"))
      (node (ref "C31") (pin "1") (pinfunction "1_1") (pintype "passive"))
      (node (ref "C32") (pin "2") (pinfunction "2_2") (pintype "passive"))
      (node (ref "C33") (pin "2") (pinfunction "2_2") (pintype "passive"))
      (node (ref "C34") (pin "1") (pinfunction "1_1") (pintype "passive"))
      (node (ref "C35") (pin "1") (pinfunction "1_1") (pintype "passive"))
      (node (ref "C36") (pin "2") (pinfunction "-_2") (pintype "passive"))
      (node (ref "C37") (pin "2") (pinfunction "-_2") (pintype "passive"))
      (node (ref "C38") (pin "2") (pinfunction "-_2") (pintype "passive"))
      (node (ref "C39") (pin "1") (pinfunction "1_1") (pintype "passive"))
      (node (ref "C40") (pin "1") (pinfunction "1_1") (pintype "passive"))
      (node (ref "C41") (pin "2") (pinfunction "-_2") (pintype "passive"))
      (node (ref "C42") (pin "1") (pinfunction "1_1") (pintype "passive"))
      (node (ref "C43") (pin "1") (pinfunction "1_1") (pintype "passive"))
      (node (ref "C5") (pin "2") (pinfunction "2_2") (pintype "passive"))
      (node (ref "C7") (pin "2") (pinfunction "2_2") (pintype "passive"))
      (node (ref "C8") (pin "2") (pinfunction "2_2") (pintype "passive"))
      (node (ref "C9") (pin "2") (pinfunction "2_2") (pintype "passive"))
      (node (ref "CS1") (pin "2") (pinfunction "-_2") (pintype "passive"))
      (node (ref "D1") (pin "2") (pinfunction "A_2") (pintype "passive"))
      (node (ref "D2") (pin "2") (pinfunction "A_2") (pintype "passive"))
      (node (ref "D3") (pin "2") (pinfunction "A_2") (pintype "passive"))
      (node (ref "DJI O3 22.2V") (pin "N") (pinfunction "N_N") (pintype "power_in"))
      (node (ref "ESC_M1 22.2V") (pin "N") (pinfunction "N_N") (pintype "power_in"))
      (node (ref "ESC_M2 22.2V") (pin "N") (pinfunction "N_N") (pintype "power_in"))
      (node (ref "ESC_M3 22.2V") (pin "N") (pinfunction "N_N") (pintype "power_in"))
      (node (ref "ESC_M4 22.2V") (pin "N") (pinfunction "N_N") (pintype "power_in"))
      (node (ref "IC1") (pin "9") (pinfunction "PGND_9") (pintype "passive"))
      (node (ref "IC2") (pin "9") (pinfunction "PGND_9") (pintype "passive"))
      (node (ref "J1") (pin "2") (pinfunction "2_2") (pintype "passive"))
      (node (ref "J2") (pin "2") (pinfunction "2_2") (pintype "passive"))
      (node (ref "J3") (pin "2") (pinfunction "2_2") (pintype "passive"))
      (node (ref "J4") (pin "2") (pinfunction "2_2") (pintype "passive"))
      (node (ref "J5") (pin "2") (pinfunction "2_2") (pintype "passive"))
      (node (ref "J8") (pin "2") (pinfunction "NEG_2") (pintype "passive"))
      (node (ref "NT1") (pin "2") (pintype "passive"))
      (node (ref "NT2") (pin "2") (pintype "passive"))
      (node (ref "R2") (pin "2") (pinfunction "2_2") (pintype "passive"))
      (node (ref "R3") (pin "2") (pinfunction "2_2") (pintype "passive"))
      (node (ref "R6") (pin "2") (pinfunction "2_2") (pintype "passive"))
      (node (ref "SIYI HM30 22.2V") (pin "N") (pinfunction "N_N") (pintype "power_in"))
      (node (ref "U1 Buck Converter") (pin "7") (pinfunction "GND_7") (pintype "passive"))
      (node (ref "U1 Buck Converter") (pin "9") (pinfunction "9_9") (pintype "passive"))
      (node (ref "UBEC jetson 22.2V") (pin "N") (pinfunction "N_N") (pintype "power_in"))
      (node (ref "extra 22.2V") (pin "N") (pinfunction "N_N") (pintype "power_in"))
    )
    (net (code "5") (name "Net-(C6-Pad2)") (class "Default")
      (node (ref "C6") (pin "2") (pinfunction "2_2") (pintype "passive"))
      (node (ref "R3") (pin "1") (pinfunction "1_1") (pintype "passive"))
    )
    (net (code "6") (name "Net-(C8-Pad1)") (class "Default")
      (node (ref "C8") (pin "1") (pinfunction "1_1") (pintype "passive"))
      (node (ref "C9") (pin "1") (pinfunction "1_1") (pintype "passive"))
      (node (ref "L1") (pin "2") (pinfunction "2_2") (pintype "passive"))
      (node (ref "L2") (pin "1") (pinfunction "1_1") (pintype "passive"))
      (node (ref "R5") (pin "1") (pinfunction "1_1") (pintype "passive"))
    )
    (net (code "7") (name "Net-(C20-Pad1)") (class "Default")
      (node (ref "C20") (pin "1") (pinfunction "1_1") (pintype "passive"))
      (node (ref "R10") (pin "2") (pinfunction "2_2") (pintype "passive"))
    )
    (net (code "8") (name "Net-(C24-Pad1)") (class "Default")
      (node (ref "C24") (pin "1") (pinfunction "1_1") (pintype "passive"))
      (node (ref "R14") (pin "1") (pinfunction "1_1") (pintype "passive"))
    )
    (net (code "9") (name "Net-(C27-+)") (class "Default")
      (node (ref "C1") (pin "2") (pinfunction "2_2") (pintype "passive"))
      (node (ref "C11") (pin "2") (pinfunction "2_2") (pintype "passive"))
      (node (ref "C12") (pin "2") (pinfunction "2_2") (pintype "passive"))
      (node (ref "C13") (pin "2") (pinfunction "2_2") (pintype "passive"))
      (node (ref "C15") (pin "2") (pinfunction "2_2") (pintype "passive"))
      (node (ref "C16") (pin "2") (pinfunction "2_2") (pintype "passive"))
      (node (ref "C17") (pin "2") (pinfunction "2_2") (pintype "passive"))
      (node (ref "C2") (pin "2") (pinfunction "2_2") (pintype "passive"))
      (node (ref "C25") (pin "2") (pinfunction "2_2") (pintype "passive"))
      (node (ref "C26") (pin "2") (pinfunction "2_2") (pintype "passive"))
      (node (ref "C27") (pin "1") (pinfunction "+_1") (pintype "passive"))
      (node (ref "C28") (pin "2") (pinfunction "2_2") (pintype "passive"))
      (node (ref "C29") (pin "2") (pinfunction "2_2") (pintype "passive"))
      (node (ref "C3") (pin "1") (pinfunction "1_1") (pintype "passive"))
      (node (ref "C30") (pin "1") (pinfunction "+_1") (pintype "passive"))
      (node (ref "C31") (pin "2") (pinfunction "2_2") (pintype "passive"))
      (node (ref "C32") (pin "1") (pinfunction "1_1") (pintype "passive"))
      (node (ref "C33") (pin "1") (pinfunction "1_1") (pintype "passive"))
      (node (ref "C34") (pin "2") (pinfunction "2_2") (pintype "passive"))
      (node (ref "C35") (pin "2") (pinfunction "2_2") (pintype "passive"))
      (node (ref "C36") (pin "1") (pinfunction "+_1") (pintype "passive"))
      (node (ref "C37") (pin "1") (pinfunction "+_1") (pintype "passive"))
      (node (ref "CS1") (pin "1") (pinfunction "+_1") (pintype "passive"))
      (node (ref "D3") (pin "1") (pinfunction "K_1") (pintype "passive"))
      (node (ref "DJI O3 22.2V") (pin "P") (pinfunction "P_P") (pintype "power_in"))
      (node (ref "ESC_M1 22.2V") (pin "P") (pinfunction "P_P") (pintype "power_in"))
      (node (ref "ESC_M2 22.2V") (pin "P") (pinfunction "P_P") (pintype "power_in"))
      (node (ref "ESC_M3 22.2V") (pin "P") (pinfunction "P_P") (pintype "power_in"))
      (node (ref "ESC_M4 22.2V") (pin "P") (pinfunction "P_P") (pintype "power_in"))
      (node (ref "IC1") (pin "11") (pinfunction "VIN_2_11") (pintype "passive"))
      (node (ref "IC1") (pin "12") (pinfunction "VIN_3_12") (pintype "passive"))
      (node (ref "IC1") (pin "13") (pinfunction "VIN_4_13") (pintype "passive"))
      (node (ref "IC1") (pin "8") (pinfunction "VIN_1_8") (pintype "passive"))
      (node (ref "IC2") (pin "11") (pinfunction "VIN_2_11") (pintype "passive"))
      (node (ref "IC2") (pin "12") (pinfunction "VIN_3_12") (pintype "passive"))
      (node (ref "IC2") (pin "13") (pinfunction "VIN_4_13") (pintype "passive"))
      (node (ref "IC2") (pin "8") (pinfunction "VIN_1_8") (pintype "passive"))
      (node (ref "J8") (pin "1") (pinfunction "POS_1") (pintype "passive"))
      (node (ref "R1") (pin "1") (pinfunction "1_1") (pintype "passive"))
      (node (ref "R4") (pin "2") (pinfunction "2_2") (pintype "passive"))
      (node (ref "R8") (pin "2") (pinfunction "2_2") (pintype "passive"))
      (node (ref "SIYI HM30 22.2V") (pin "P") (pinfunction "P_P") (pintype "power_in"))
      (node (ref "U1 Buck Converter") (pin "2") (pinfunction "VIN_2") (pintype "passive"))
      (node (ref "UBEC jetson 22.2V") (pin "P") (pinfunction "P_P") (pintype "power_in"))
      (node (ref "extra 22.2V") (pin "P") (pinfunction "P_P") (pintype "power_in"))
    )
    (net (code "10") (name "Net-(C38-+)") (class "Default")
      (node (ref "C18") (pin "2") (pinfunction "2_2") (pintype "passive"))
      (node (ref "C19") (pin "2") (pinfunction "2_2") (pintype "passive"))
      (node (ref "C38") (pin "1") (pinfunction "+_1") (pintype "passive"))
      (node (ref "C39") (pin "2") (pinfunction "2_2") (pintype "passive"))
      (node (ref "C40") (pin "2") (pinfunction "2_2") (pintype "passive"))
      (node (ref "J1") (pin "1") (pinfunction "1_1") (pintype "passive"))
      (node (ref "J2") (pin "1") (pinfunction "1_1") (pintype "passive"))
      (node (ref "L3") (pin "1") (pinfunction "1_1") (pintype "passive"))
      (node (ref "R9") (pin "2") (pinfunction "2_2") (pintype "passive"))
    )
    (net (code "11") (name "Net-(C41-+)") (class "Default")
      (node (ref "C22") (pin "2") (pinfunction "2_2") (pintype "passive"))
      (node (ref "C23") (pin "2") (pinfunction "2_2") (pintype "passive"))
      (node (ref "C41") (pin "1") (pinfunction "+_1") (pintype "passive"))
      (node (ref "C42") (pin "2") (pinfunction "2_2") (pintype "passive"))
      (node (ref "C43") (pin "2") (pinfunction "2_2") (pintype "passive"))
      (node (ref "J3") (pin "1") (pinfunction "1_1") (pintype "passive"))
      (node (ref "J4") (pin "1") (pinfunction "1_1") (pintype "passive"))
      (node (ref "L4") (pin "1") (pinfunction "1_1") (pintype "passive"))
      (node (ref "R13") (pin "2") (pinfunction "2_2") (pintype "passive"))
    )
    (net (code "12") (name "Net-(D1-K)") (class "Default")
      (node (ref "C4") (pin "1") (pinfunction "1_1") (pintype "passive"))
      (node (ref "D1") (pin "1") (pinfunction "K_1") (pintype "passive"))
      (node (ref "L1") (pin "1") (pinfunction "1_1") (pintype "passive"))
      (node (ref "U1 Buck Converter") (pin "8") (pinfunction "PH_8") (pintype "passive"))
    )
    (net (code "13") (name "Net-(IC1-BOOT)") (class "Default")
      (node (ref "C14") (pin "1") (pinfunction "1_1") (pintype "passive"))
      (node (ref "IC1") (pin "7") (pinfunction "BOOT_7") (pintype "passive"))
    )
    (net (code "14") (name "Net-(IC1-EN)") (class "Default")
      (node (ref "IC1") (pin "1") (pinfunction "EN_1") (pintype "passive"))
      (node (ref "R4") (pin "1") (pinfunction "1_1") (pintype "passive"))
      (node (ref "R7") (pin "2") (pinfunction "2_2") (pintype "passive"))
    )
    (net (code "15") (name "Net-(IC1-FB)") (class "Default")
      (node (ref "C20") (pin "2") (pinfunction "2_2") (pintype "passive"))
      (node (ref "IC1") (pin "2") (pinfunction "FB_2") (pintype "passive"))
      (node (ref "P1") (pin "1") (pinfunction "CCW_1") (pintype "passive"))
      (node (ref "P1") (pin "2") (pinfunction "WIPER_2") (pintype "passive"))
      (node (ref "R15") (pin "2") (pinfunction "2_2") (pintype "passive"))
    )
    (net (code "16") (name "Net-(IC1-SW)") (class "Default")
      (node (ref "C14") (pin "2") (pinfunction "2_2") (pintype "passive"))
      (node (ref "IC1") (pin "6") (pinfunction "SW_6") (pintype "passive"))
      (node (ref "L3") (pin "2") (pinfunction "2_2") (pintype "passive"))
    )
    (net (code "17") (name "Net-(IC2-BOOT)") (class "Default")
      (node (ref "C21") (pin "1") (pinfunction "1_1") (pintype "passive"))
      (node (ref "IC2") (pin "7") (pinfunction "BOOT_7") (pintype "passive"))
    )
    (net (code "18") (name "Net-(IC2-EN)") (class "Default")
      (node (ref "IC2") (pin "1") (pinfunction "EN_1") (pintype "passive"))
      (node (ref "R11") (pin "2") (pinfunction "2_2") (pintype "passive"))
      (node (ref "R8") (pin "1") (pinfunction "1_1") (pintype "passive"))
    )
    (net (code "19") (name "Net-(IC2-FB)") (class "Default")
      (node (ref "C24") (pin "2") (pinfunction "2_2") (pintype "passive"))
      (node (ref "IC2") (pin "2") (pinfunction "FB_2") (pintype "passive"))
      (node (ref "R16") (pin "1") (pinfunction "1_1") (pintype "passive"))
      (node (ref "R17") (pin "2") (pinfunction "2_2") (pintype "passive"))
    )
    (net (code "20") (name "Net-(IC2-SW)") (class "Default")
      (node (ref "C21") (pin "2") (pinfunction "2_2") (pintype "passive"))
      (node (ref "IC2") (pin "6") (pinfunction "SW_6") (pintype "passive"))
      (node (ref "L4") (pin "2") (pinfunction "2_2") (pintype "passive"))
    )
    (net (code "21") (name "Net-(P1-CW)") (class "Default")
      (node (ref "P1") (pin "3") (pinfunction "CW_3") (pintype "passive"))
      (node (ref "R12") (pin "1") (pinfunction "1_1") (pintype "passive"))
    )
    (net (code "22") (name "Net-(R10-Pad1)") (class "Default")
      (node (ref "R10") (pin "1") (pinfunction "1_1") (pintype "passive"))
      (node (ref "R12") (pin "2") (pinfunction "2_2") (pintype "passive"))
      (node (ref "R9") (pin "1") (pinfunction "1_1") (pintype "passive"))
    )
    (net (code "23") (name "Net-(R13-Pad1)") (class "Default")
      (node (ref "R13") (pin "1") (pinfunction "1_1") (pintype "passive"))
      (node (ref "R14") (pin "2") (pinfunction "2_2") (pintype "passive"))
      (node (ref "R16") (pin "2") (pinfunction "2_2") (pintype "passive"))
    )
    (net (code "24") (name "Net-(U1 Buck Converter-BOOT)") (class "Default")
      (node (ref "C4") (pin "2") (pinfunction "2_2") (pintype "passive"))
      (node (ref "U1 Buck Converter") (pin "1") (pinfunction "BOOT_1") (pintype "passive"))
    )
    (net (code "25") (name "Net-(U1 Buck Converter-COMP)") (class "Default")
      (node (ref "C6") (pin "1") (pinfunction "1_1") (pintype "passive"))
      (node (ref "C7") (pin "1") (pinfunction "1_1") (pintype "passive"))
      (node (ref "U1 Buck Converter") (pin "6") (pinfunction "COMP_6") (pintype "passive"))
    )
    (net (code "26") (name "Net-(U1 Buck Converter-EN)") (class "Default")
      (node (ref "R1") (pin "2") (pinfunction "2_2") (pintype "passive"))
      (node (ref "R2") (pin "1") (pinfunction "1_1") (pintype "passive"))
      (node (ref "U1 Buck Converter") (pin "3") (pinfunction "EN_3") (pintype "passive"))
    )
    (net (code "27") (name "Net-(U1 Buck Converter-SS)") (class "Default")
      (node (ref "C5") (pin "1") (pinfunction "1_1") (pintype "passive"))
      (node (ref "U1 Buck Converter") (pin "4") (pinfunction "SS_4") (pintype "passive"))
    )
    (net (code "28") (name "Net-(U1 Buck Converter-VSENSE)") (class "Default")
      (node (ref "R5") (pin "2") (pinfunction "2_2") (pintype "passive"))
      (node (ref "R6") (pin "1") (pinfunction "1_1") (pintype "passive"))
      (node (ref "U1 Buck Converter") (pin "5") (pinfunction "VSENSE_5") (pintype "passive"))
    )
    (net (code "29") (name "unconnected-(IC1-NC-Pad5)") (class "Default")
      (node (ref "IC1") (pin "5") (pinfunction "NC_5") (pintype "passive+no_connect"))
    )
    (net (code "30") (name "unconnected-(IC1-PG-Pad4)") (class "Default")
      (node (ref "IC1") (pin "4") (pinfunction "PG_4") (pintype "passive+no_connect"))
    )
    (net (code "31") (name "unconnected-(IC2-NC-Pad5)") (class "Default")
      (node (ref "IC2") (pin "5") (pinfunction "NC_5") (pintype "passive+no_connect"))
    )
    (net (code "32") (name "unconnected-(IC2-PG-Pad4)") (class "Default")
      (node (ref "IC2") (pin "4") (pinfunction "PG_4") (pintype "passive+no_connect"))
    )
  )
)
